# AQCA-Light-Control-WarmWhite-A0.net
KiCad netlist of a schematic drawn in Altium Designer
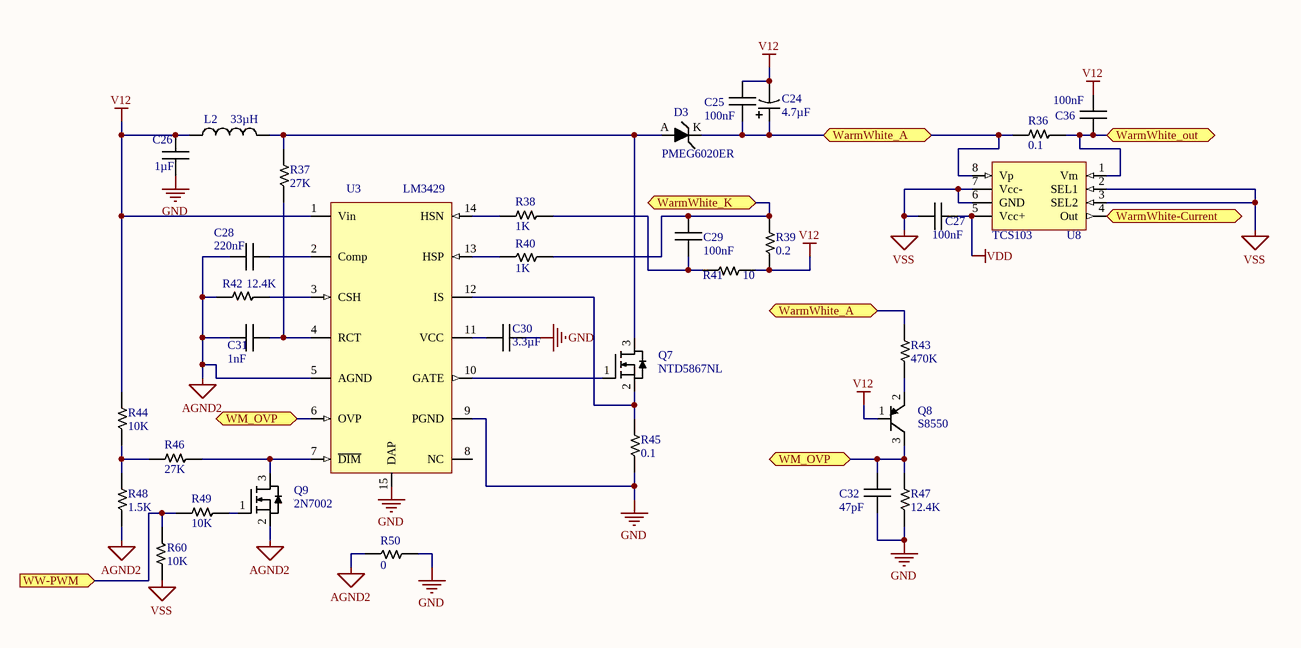
[diagram p0: AQCA-Light-Control-WarmWhite-A0.SchDoc]

(export (version "E")
  (design (tool "Eeschema 10.0.6"))
  (components
    (comp (ref "C24")
      (value "4.7µF")
      (footprint "CAPPR2-5x11")
      (fields (field (name "VOLTAGE") "100V"))
      (libsource (lib "Megaxone") (part "Capacitor Polarised"))
    )
    (comp (ref "C25")
      (value "100nF")
      (footprint "CAPC2012N")
      (fields (field (name "VOLTAGE") "100V"))
      (libsource (lib "Megaxone") (part "Capacitor"))
    )
    (comp (ref "C26")
      (value "1µF")
      (footprint "CAPC1608N")
      (fields (field (name "VOLTAGE") "25V"))
      (libsource (lib "Megaxone") (part "Capacitor"))
    )
    (comp (ref "C27")
      (value "100nF")
      (footprint "CAPC1608N")
      (fields (field (name "VOLTAGE") "16V"))
      (libsource (lib "Megaxone") (part "Capacitor"))
    )
    (comp (ref "C28")
      (value "220nF")
      (footprint "CAPC1608N")
      (fields (field (name "VOLTAGE") "25V"))
      (libsource (lib "Megaxone") (part "Capacitor"))
    )
    (comp (ref "C29")
      (value "100nF")
      (footprint "CAPC1608N")
      (fields (field (name "VOLTAGE") "50V"))
      (libsource (lib "Megaxone") (part "Capacitor"))
    )
    (comp (ref "C30")
      (value "3.3µF")
      (footprint "CAPC1608N")
      (fields (field (name "VOLTAGE") "16V"))
      (libsource (lib "Megaxone") (part "Capacitor"))
    )
    (comp (ref "C31")
      (value "1nF")
      (footprint "CAPC1608N")
      (fields (field (name "VOLTAGE") "50V"))
      (libsource (lib "Megaxone") (part "Capacitor"))
    )
    (comp (ref "C32")
      (value "47pF")
      (footprint "CAPC1608N")
      (fields (field (name "VOLTAGE") "100V"))
      (libsource (lib "Megaxone") (part "Capacitor"))
    )
    (comp (ref "C36")
      (value "100nF")
      (footprint "CAPC2012N")
      (fields (field (name "VOLTAGE") "100V"))
      (libsource (lib "Megaxone") (part "Capacitor"))
    )
    (comp (ref "D3")
      (value "PMEG6020ER")
      (footprint "SOD123")
      (libsource (lib "Megaxone") (part "Schottky Diode"))
    )
    (comp (ref "L2")
      (value "33µH")
      (footprint "Inductor AIUR5-6")
      (libsource (lib "Megaxone") (part "Inductor"))
    )
    (comp (ref "Q7")
      (value "NTD5867NL")
      (footprint "DPAK 369AA")
      (libsource (lib "Megaxone") (part "MOSFET N-Ch"))
    )
    (comp (ref "Q8") (value "S8550") (footprint "SOT23_N") (libsource (lib "Megaxone") (part "PNP")))
    (comp (ref "Q9")
      (value "2N7002")
      (footprint "SOT23-3N")
      (libsource (lib "Megaxone") (part "MOSFET N-Ch"))
    )
    (comp (ref "R36") (value "0.1") (footprint "RESC2012N") (libsource (lib "") (part "Resistor_1")))
    (comp (ref "R37") (value "27K") (footprint "RESC1608N") (libsource (lib "Megaxone") (part "Resistor")))
    (comp (ref "R38") (value "1K") (footprint "RESC1608N") (libsource (lib "") (part "Resistor_1")))
    (comp (ref "R39") (value "0.2") (footprint "RESC6332N") (libsource (lib "Megaxone") (part "Resistor")))
    (comp (ref "R40") (value "1K") (footprint "RESC1608N") (libsource (lib "") (part "Resistor_2")))
    (comp (ref "R41") (value "10") (footprint "RESC1608N") (libsource (lib "") (part "Resistor_2")))
    (comp (ref "R42") (value "12.4K") (footprint "RESC1608N") (libsource (lib "") (part "Resistor_1")))
    (comp (ref "R43") (value "470K") (footprint "RESC1608N") (libsource (lib "Megaxone") (part "Resistor")))
    (comp (ref "R44") (value "10K") (footprint "RESC1608N") (libsource (lib "Megaxone") (part "Resistor")))
    (comp (ref "R45") (value "0.1") (footprint "RESC6332N") (libsource (lib "Megaxone") (part "Resistor")))
    (comp (ref "R46") (value "27K") (footprint "RESC1608N") (libsource (lib "") (part "Resistor_1")))
    (comp (ref "R47") (value "12.4K") (footprint "RESC1608N") (libsource (lib "Megaxone") (part "Resistor")))
    (comp (ref "R48") (value "1.5K") (footprint "RESC1608N") (libsource (lib "Megaxone") (part "Resistor")))
    (comp (ref "R49") (value "10K") (footprint "RESC1608N") (libsource (lib "") (part "Resistor_1")))
    (comp (ref "R50") (value "0") (footprint "RESC1608N") (libsource (lib "") (part "Resistor_2")))
    (comp (ref "R60") (value "10K") (footprint "RESC1608N") (libsource (lib "") (part "Resistor_3")))
    (comp (ref "U3")
      (value "LM3429")
      (footprint "TSOP65P640_HS-14N")
      (libsource (lib "Megaxone") (part "LM3429"))
    )
    (comp (ref "U8") (value "TCS103") (footprint "TSSOP8N_N") (libsource (lib "Megaxone") (part "TCS103")))
  )
  (nets
    (net (code "1") (name "/WM_OVP") (class "Default")
      (node (ref "C32") (pin "2") (pinfunction "2_2") (pintype "passive"))
      (node (ref "Q8") (pin "3") (pinfunction "C_3") (pintype "passive"))
      (node (ref "R47") (pin "2") (pinfunction "2_2") (pintype "passive"))
      (node (ref "U3") (pin "6") (pinfunction "OVP_6") (pintype "input"))
    )
    (net (code "2") (name "/WW-PWM") (class "Default")
      (node (ref "R49") (pin "2") (pinfunction "2_2") (pintype "passive"))
      (node (ref "R60") (pin "1") (pinfunction "1_1") (pintype "passive"))
    )
    (net (code "3") (name "/WarmWhite-Current") (class "Default")
      (node (ref "U8") (pin "4") (pinfunction "Out_4") (pintype "output"))
    )
    (net (code "4") (name "/WarmWhite_A") (class "Default")
      (node (ref "C24") (pin "1") (pinfunction "1_1") (pintype "passive"))
      (node (ref "C25") (pin "1") (pinfunction "1_1") (pintype "passive"))
      (node (ref "D3") (pin "K") (pinfunction "Kathode_K") (pintype "power_in"))
      (node (ref "R36") (pin "2") (pinfunction "2_2") (pintype "passive"))
      (node (ref "R43") (pin "2") (pinfunction "2_2") (pintype "passive"))
      (node (ref "U8") (pin "8") (pinfunction "Vp_8") (pintype "input"))
    )
    (net (code "5") (name "/WarmWhite_K") (class "Default")
      (node (ref "C29") (pin "2") (pinfunction "2_2") (pintype "passive"))
      (node (ref "R39") (pin "2") (pinfunction "2_2") (pintype "passive"))
      (node (ref "R40") (pin "2") (pinfunction "2_2") (pintype "passive"))
    )
    (net (code "6") (name "/WarmWhite_out") (class "Default")
      (node (ref "C36") (pin "1") (pinfunction "1_1") (pintype "passive"))
      (node (ref "R36") (pin "1") (pinfunction "1_1") (pintype "passive"))
      (node (ref "U8") (pin "1") (pinfunction "Vm_1") (pintype "input"))
    )
    (net (code "7") (name "AGND2") (class "Default")
      (node (ref "C28") (pin "1") (pinfunction "1_1") (pintype "passive"))
      (node (ref "C31") (pin "1") (pinfunction "1_1") (pintype "passive"))
      (node (ref "Q9") (pin "2") (pinfunction "S_2") (pintype "passive"))
      (node (ref "R42") (pin "2") (pinfunction "2_2") (pintype "passive"))
      (node (ref "R48") (pin "1") (pinfunction "1_1") (pintype "passive"))
      (node (ref "R50") (pin "1") (pinfunction "1_1") (pintype "passive"))
      (node (ref "U3") (pin "5") (pinfunction "AGND_5") (pintype "power_in"))
    )
    (net (code "8") (name "GND") (class "Default")
      (node (ref "C26") (pin "1") (pinfunction "1_1") (pintype "passive"))
      (node (ref "C30") (pin "1") (pinfunction "1_1") (pintype "passive"))
      (node (ref "C32") (pin "1") (pinfunction "1_1") (pintype "passive"))
      (node (ref "R45") (pin "1") (pinfunction "1_1") (pintype "passive"))
      (node (ref "R47") (pin "1") (pinfunction "1_1") (pintype "passive"))
      (node (ref "R50") (pin "2") (pinfunction "2_2") (pintype "passive"))
      (node (ref "U3") (pin "15") (pinfunction "DAP_15") (pintype "passive"))
      (node (ref "U3") (pin "9") (pinfunction "PGND_9") (pintype "power_in"))
    )
    (net (code "9") (name "Net-(C29-Pad1)") (class "Default")
      (node (ref "C29") (pin "1") (pinfunction "1_1") (pintype "passive"))
      (node (ref "R38") (pin "1") (pinfunction "1_1") (pintype "passive"))
      (node (ref "R41") (pin "1") (pinfunction "1_1") (pintype "passive"))
    )
    (net (code "10") (name "Net-(D3-Anode)") (class "Default")
      (node (ref "D3") (pin "A") (pinfunction "Anode_A") (pintype "power_in"))
      (node (ref "L2") (pin "2") (pinfunction "2_2") (pintype "passive"))
      (node (ref "Q7") (pin "3") (pinfunction "D_3") (pintype "passive"))
      (node (ref "R37") (pin "2") (pinfunction "2_2") (pintype "passive"))
    )
    (net (code "11") (name "Net-(Q7-G)") (class "Default")
      (node (ref "Q7") (pin "1") (pinfunction "G_1") (pintype "passive"))
      (node (ref "U3") (pin "10") (pinfunction "GATE_10") (pintype "output"))
    )
    (net (code "12") (name "Net-(Q7-S)") (class "Default")
      (node (ref "Q7") (pin "2") (pinfunction "S_2") (pintype "passive"))
      (node (ref "R45") (pin "2") (pinfunction "2_2") (pintype "passive"))
      (node (ref "U3") (pin "12") (pinfunction "IS_12") (pintype "passive"))
    )
    (net (code "13") (name "Net-(Q8-E)") (class "Default")
      (node (ref "Q8") (pin "2") (pinfunction "E_2") (pintype "passive"))
      (node (ref "R43") (pin "1") (pinfunction "1_1") (pintype "passive"))
    )
    (net (code "14") (name "Net-(Q9-D)") (class "Default")
      (node (ref "Q9") (pin "3") (pinfunction "D_3") (pintype "passive"))
      (node (ref "R46") (pin "1") (pinfunction "1_1") (pintype "passive"))
      (node (ref "U3") (pin "7") (pinfunction "~{DIM}_7") (pintype "input"))
    )
    (net (code "15") (name "Net-(Q9-G)") (class "Default")
      (node (ref "Q9") (pin "1") (pinfunction "G_1") (pintype "passive"))
      (node (ref "R49") (pin "1") (pinfunction "1_1") (pintype "passive"))
    )
    (net (code "16") (name "Net-(R44-Pad1)") (class "Default")
      (node (ref "R44") (pin "1") (pinfunction "1_1") (pintype "passive"))
      (node (ref "R46") (pin "2") (pinfunction "2_2") (pintype "passive"))
      (node (ref "R48") (pin "2") (pinfunction "2_2") (pintype "passive"))
    )
    (net (code "17") (name "Net-(U3-CSH)") (class "Default")
      (node (ref "R42") (pin "1") (pinfunction "1_1") (pintype "passive"))
      (node (ref "U3") (pin "3") (pinfunction "CSH_3") (pintype "input"))
    )
    (net (code "18") (name "Net-(U3-Comp)") (class "Default")
      (node (ref "C28") (pin "2") (pinfunction "2_2") (pintype "passive"))
      (node (ref "U3") (pin "2") (pinfunction "Comp_2") (pintype "passive"))
    )
    (net (code "19") (name "Net-(U3-HSN)") (class "Default")
      (node (ref "R38") (pin "2") (pinfunction "2_2") (pintype "passive"))
      (node (ref "U3") (pin "14") (pinfunction "HSN_14") (pintype "input"))
    )
    (net (code "20") (name "Net-(U3-HSP)") (class "Default")
      (node (ref "R40") (pin "1") (pinfunction "1_1") (pintype "passive"))
      (node (ref "U3") (pin "13") (pinfunction "HSP_13") (pintype "input"))
    )
    (net (code "21") (name "Net-(U3-RCT)") (class "Default")
      (node (ref "C31") (pin "2") (pinfunction "2_2") (pintype "passive"))
      (node (ref "R37") (pin "1") (pinfunction "1_1") (pintype "passive"))
      (node (ref "U3") (pin "4") (pinfunction "RCT_4") (pintype "passive"))
    )
    (net (code "22") (name "Net-(U3-VCC)") (class "Default")
      (node (ref "C30") (pin "2") (pinfunction "2_2") (pintype "passive"))
      (node (ref "U3") (pin "11") (pinfunction "VCC_11") (pintype "power_in"))
    )
    (net (code "23") (name "V12") (class "Default")
      (node (ref "C24") (pin "2") (pinfunction "2_2") (pintype "passive"))
      (node (ref "C25") (pin "2") (pinfunction "2_2") (pintype "passive"))
      (node (ref "C26") (pin "2") (pinfunction "2_2") (pintype "passive"))
      (node (ref "C36") (pin "2") (pinfunction "2_2") (pintype "passive"))
      (node (ref "L2") (pin "1") (pinfunction "1_1") (pintype "passive"))
      (node (ref "Q8") (pin "1") (pinfunction "B_1") (pintype "passive"))
      (node (ref "R39") (pin "1") (pinfunction "1_1") (pintype "passive"))
      (node (ref "R41") (pin "2") (pinfunction "2_2") (pintype "passive"))
      (node (ref "R44") (pin "2") (pinfunction "2_2") (pintype "passive"))
      (node (ref "U3") (pin "1") (pinfunction "Vin_1") (pintype "power_in"))
    )
    (net (code "24") (name "VDD") (class "Default")
      (node (ref "C27") (pin "1") (pinfunction "1_1") (pintype "passive"))
      (node (ref "U8") (pin "5") (pinfunction "Vcc+_5") (pintype "power_in"))
    )
    (net (code "25") (name "VSS") (class "Default")
      (node (ref "C27") (pin "2") (pinfunction "2_2") (pintype "passive"))
      (node (ref "R60") (pin "2") (pinfunction "2_2") (pintype "passive"))
      (node (ref "U8") (pin "2") (pinfunction "SEL1_2") (pintype "input"))
      (node (ref "U8") (pin "3") (pinfunction "SEL2_3") (pintype "input"))
      (node (ref "U8") (pin "6") (pinfunction "GND_6") (pintype "power_in"))
      (node (ref "U8") (pin "7") (pinfunction "Vcc-_7") (pintype "power_in"))
    )
    (net (code "26") (name "unconnected-(U3-NC-Pad8)") (class "Default")
      (node (ref "U3") (pin "8") (pinfunction "NC_8") (pintype "passive"))
    )
  )
)
